# ps_adjustable_hv.net
KiCad netlist of a schematic drawn in EAGLE
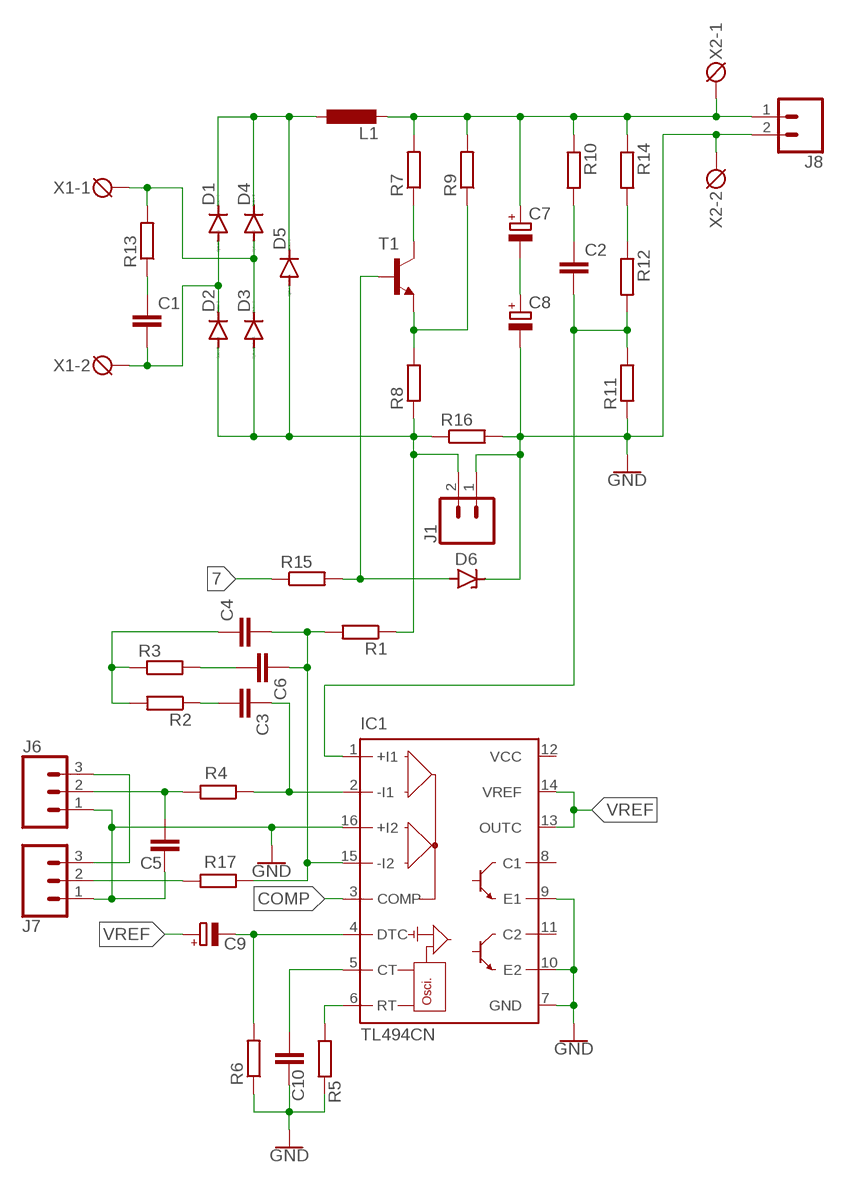
[diagram p0: schematic, sheet 1]

(export (version "E")
  (design (tool "Eeschema 10.0.6"))
  (components
    (comp (ref "C1")
      (value "C-EU050-045X075")
      (footprint "eagle-import:C050-045X075")
      (libsource (lib "eagle-import") (part "rcl_modify_C-EU050-045X075"))
    )
    (comp (ref "C2")
      (value "C-EU102-064X133")
      (footprint "eagle-import:C102-064X133")
      (libsource (lib "eagle-import") (part "rcl_modify_C-EU102-064X133"))
    )
    (comp (ref "C3")
      (value "C-EUC0805")
      (footprint "eagle-import:C0805")
      (libsource (lib "eagle-import") (part "C-EUC0805"))
    )
    (comp (ref "C4")
      (value "C-EUC0805")
      (footprint "eagle-import:C0805")
      (libsource (lib "eagle-import") (part "C-EUC0805"))
    )
    (comp (ref "C5")
      (value "C-EUC0805")
      (footprint "eagle-import:C0805")
      (libsource (lib "eagle-import") (part "C-EUC0805"))
    )
    (comp (ref "C6")
      (value "C-EUC0805")
      (footprint "eagle-import:C0805")
      (libsource (lib "eagle-import") (part "C-EUC0805"))
    )
    (comp (ref "C7")
      (value "CPOL-EUE10-20")
      (footprint "eagle-import:EB20D")
      (libsource (lib "eagle-import") (part "CPOL-EUE10-20"))
    )
    (comp (ref "C8")
      (value "CPOL-EUE10-20")
      (footprint "eagle-import:EB20D")
      (libsource (lib "eagle-import") (part "CPOL-EUE10-20"))
    )
    (comp (ref "C9")
      (value "CPOL-EUE2.5-6")
      (footprint "eagle-import:E2,5-6")
      (libsource (lib "eagle-import") (part "CPOL-EUE2.5-6"))
    )
    (comp (ref "C10")
      (value "C-EUC0805")
      (footprint "eagle-import:C0805")
      (libsource (lib "eagle-import") (part "C-EUC0805"))
    )
    (comp (ref "D1")
      (value "UF4003")
      (footprint "eagle-import:DO41-10")
      (libsource (lib "eagle-import") (part "UF4003"))
    )
    (comp (ref "D2")
      (value "UF4003")
      (footprint "eagle-import:DO41-10")
      (libsource (lib "eagle-import") (part "UF4003"))
    )
    (comp (ref "D3")
      (value "UF4003")
      (footprint "eagle-import:DO41-10")
      (libsource (lib "eagle-import") (part "UF4003"))
    )
    (comp (ref "D4")
      (value "UF4003")
      (footprint "eagle-import:DO41-10")
      (libsource (lib "eagle-import") (part "UF4003"))
    )
    (comp (ref "D5")
      (value "UF4003")
      (footprint "eagle-import:DO41-10")
      (libsource (lib "eagle-import") (part "UF4003"))
    )
    (comp (ref "D6")
      (value "ZENER-DIODEP1-Z12")
      (footprint "eagle-import:P1Z12")
      (libsource (lib "eagle-import") (part "ZENER-DIODEP1-Z12"))
    )
    (comp (ref "IC1")
      (value "TL494CN")
      (footprint "eagle-import:DIL16")
      (libsource (lib "eagle-import") (part "TL494NC"))
    )
    (comp (ref "J1")
      (value "CONN_02")
      (footprint "eagle-import:1X02")
      (libsource (lib "eagle-import") (part "CONN_02"))
    )
    (comp (ref "J6")
      (value "455-1750-1-ND")
      (footprint "eagle-import:1X03")
      (libsource (lib "eagle-import") (part "CONN_03"))
    )
    (comp (ref "J7")
      (value "455-1750-1-ND")
      (footprint "eagle-import:1X03")
      (libsource (lib "eagle-import") (part "CONN_03"))
    )
    (comp (ref "J8")
      (value "CONN_02")
      (footprint "eagle-import:1X02")
      (libsource (lib "eagle-import") (part "CONN_02"))
    )
    (comp (ref "L1")
      (value "L-EUTJ5-U1")
      (footprint "eagle-import:TJ5-U1")
      (libsource (lib "eagle-import") (part "L-EUTJ5-U1"))
    )
    (comp (ref "R1")
      (value "R-EU_R0805")
      (footprint "eagle-import:R0805")
      (libsource (lib "eagle-import") (part "R-EU_R0805"))
    )
    (comp (ref "R2")
      (value "R-EU_R0805")
      (footprint "eagle-import:R0805")
      (libsource (lib "eagle-import") (part "R-EU_R0805"))
    )
    (comp (ref "R3")
      (value "R-EU_VMTA55")
      (footprint "eagle-import:VMTA55")
      (libsource (lib "eagle-import") (part "rcl_modify_R-EU_VMTA55"))
    )
    (comp (ref "R4")
      (value "R-EU_VMTA55")
      (footprint "eagle-import:VMTA55")
      (libsource (lib "eagle-import") (part "rcl_modify_R-EU_VMTA55"))
    )
    (comp (ref "R5")
      (value "R-EU_R0805")
      (footprint "eagle-import:R0805")
      (libsource (lib "eagle-import") (part "R-EU_R0805"))
    )
    (comp (ref "R6")
      (value "R-EU_R0805")
      (footprint "eagle-import:R0805")
      (libsource (lib "eagle-import") (part "R-EU_R0805"))
    )
    (comp (ref "R7")
      (value "R-EU_VMTA55")
      (footprint "eagle-import:VMTA55")
      (libsource (lib "eagle-import") (part "rcl_modify_R-EU_VMTA55"))
    )
    (comp (ref "R8")
      (value "R-EU_VMTA55")
      (footprint "eagle-import:VMTA55")
      (libsource (lib "eagle-import") (part "rcl_modify_R-EU_VMTA55"))
    )
    (comp (ref "R9")
      (value "R-EU_VMTA55")
      (footprint "eagle-import:VMTA55")
      (libsource (lib "eagle-import") (part "rcl_modify_R-EU_VMTA55"))
    )
    (comp (ref "R10")
      (value "R-EU_VMTA55")
      (footprint "eagle-import:VMTA55")
      (libsource (lib "eagle-import") (part "rcl_modify_R-EU_VMTA55"))
    )
    (comp (ref "R11")
      (value "R-EU_VMTA55")
      (footprint "eagle-import:VMTA55")
      (libsource (lib "eagle-import") (part "rcl_modify_R-EU_VMTA55"))
    )
    (comp (ref "R12")
      (value "R-EU_VMTA55")
      (footprint "eagle-import:VMTA55")
      (libsource (lib "eagle-import") (part "rcl_modify_R-EU_VMTA55"))
    )
    (comp (ref "R13")
      (value "R-EU_VMTB60")
      (footprint "eagle-import:VMTB60")
      (libsource (lib "eagle-import") (part "rcl_modify_R-EU_VMTB60"))
    )
    (comp (ref "R14")
      (value "R-EU_VTA53")
      (footprint "eagle-import:VTA53")
      (libsource (lib "eagle-import") (part "rcl_modify_R-EU_VTA53"))
    )
    (comp (ref "R15")
      (value "R-EU_VMTA55")
      (footprint "eagle-import:VMTA55")
      (libsource (lib "eagle-import") (part "rcl_modify_R-EU_VMTA55"))
    )
    (comp (ref "R16")
      (value "R-EU_VTA53")
      (footprint "eagle-import:VTA53")
      (libsource (lib "eagle-import") (part "rcl_modify_R-EU_VTA53"))
    )
    (comp (ref "R17")
      (value "R-EU_VMTA55")
      (footprint "eagle-import:VMTA55")
      (libsource (lib "eagle-import") (part "rcl_modify_R-EU_VMTA55"))
    )
    (comp (ref "T1")
      (value "2N6517-NPN-TO92-CBE")
      (footprint "eagle-import:TO92-CBE")
      (libsource (lib "eagle-import") (part "-NPN-TO92-CBE2N6517"))
    )
    (comp (ref "X1")
      (value "DG3XX-02-5.0")
      (footprint "eagle-import:DG306-5.0-02P")
      (libsource (lib "eagle-import") (part "DG3XX-02-5.0"))
    )
    (comp (ref "X2")
      (value "DG3XX-02-5.0")
      (footprint "eagle-import:DG306-5.0-02P")
      (libsource (lib "eagle-import") (part "DG3XX-02-5.0"))
    )
  )
  (nets
    (net (code "1") (name "/VCC") (class "Default")
      (node (ref "IC1") (pin "12") (pinfunction "VCC_12") (pintype "power_in"))
    )
    (net (code "2") (name "7") (class "Default")
      (node (ref "R15") (pin "1") (pinfunction "1_1") (pintype "passive"))
    )
    (net (code "3") (name "COMP") (class "Default")
      (node (ref "IC1") (pin "3") (pinfunction "COMP_3") (pintype "passive"))
    )
    (net (code "4") (name "GND") (class "Default")
      (node (ref "C10") (pin "1") (pinfunction "1_1") (pintype "passive"))
      (node (ref "C5") (pin "2") (pinfunction "2_2") (pintype "passive"))
      (node (ref "C8") (pin "-") (pinfunction "-_-") (pintype "passive"))
      (node (ref "D6") (pin "C") (pinfunction "C_C") (pintype "passive"))
      (node (ref "IC1") (pin "10") (pinfunction "E2_10") (pintype "passive"))
      (node (ref "IC1") (pin "16") (pinfunction "+I2_16") (pintype "input"))
      (node (ref "IC1") (pin "7") (pinfunction "GND_7") (pintype "power_in"))
      (node (ref "IC1") (pin "9") (pinfunction "E1_9") (pintype "passive"))
      (node (ref "J1") (pin "1") (pinfunction "1_1") (pintype "passive"))
      (node (ref "J6") (pin "1") (pinfunction "1_1") (pintype "passive"))
      (node (ref "J7") (pin "1") (pinfunction "1_1") (pintype "passive"))
      (node (ref "J8") (pin "2") (pinfunction "2_2") (pintype "passive"))
      (node (ref "R11") (pin "1") (pinfunction "1_1") (pintype "passive"))
      (node (ref "R16") (pin "2") (pinfunction "2_2") (pintype "passive"))
      (node (ref "R5") (pin "2") (pinfunction "2_2") (pintype "passive"))
      (node (ref "R6") (pin "1") (pinfunction "1_1") (pintype "passive"))
      (node (ref "X2") (pin "2") (pinfunction "KL_2") (pintype "passive"))
    )
    (net (code "5") (name "Net-(C1-Pad1)") (class "Default")
      (node (ref "C1") (pin "1") (pinfunction "1_1") (pintype "passive"))
      (node (ref "R13") (pin "1") (pinfunction "1_1") (pintype "passive"))
    )
    (net (code "6") (name "Net-(C2-Pad1)") (class "Default")
      (node (ref "C2") (pin "1") (pinfunction "1_1") (pintype "passive"))
      (node (ref "R10") (pin "2") (pinfunction "2_2") (pintype "passive"))
    )
    (net (code "7") (name "Net-(C3-Pad2)") (class "Default")
      (node (ref "C3") (pin "2") (pinfunction "2_2") (pintype "passive"))
      (node (ref "R2") (pin "1") (pinfunction "1_1") (pintype "passive"))
    )
    (net (code "8") (name "Net-(C4-Pad1)") (class "Default")
      (node (ref "C4") (pin "1") (pinfunction "1_1") (pintype "passive"))
      (node (ref "R2") (pin "2") (pinfunction "2_2") (pintype "passive"))
      (node (ref "R3") (pin "1") (pinfunction "1_1") (pintype "passive"))
    )
    (net (code "9") (name "Net-(C5-Pad1)") (class "Default")
      (node (ref "C5") (pin "1") (pinfunction "1_1") (pintype "passive"))
      (node (ref "J6") (pin "2") (pinfunction "2_2") (pintype "passive"))
      (node (ref "R4") (pin "2") (pinfunction "2_2") (pintype "passive"))
    )
    (net (code "10") (name "Net-(C6-Pad2)") (class "Default")
      (node (ref "C6") (pin "2") (pinfunction "2_2") (pintype "passive"))
      (node (ref "R3") (pin "2") (pinfunction "2_2") (pintype "passive"))
    )
    (net (code "11") (name "Net-(C7-Pad-)") (class "Default")
      (node (ref "C7") (pin "-") (pinfunction "-_-") (pintype "passive"))
      (node (ref "C8") (pin "+") (pinfunction "+_+") (pintype "passive"))
    )
    (net (code "12") (name "Net-(D1-PadC)") (class "Default")
      (node (ref "D1") (pin "C") (pinfunction "C_C") (pintype "passive"))
      (node (ref "D4") (pin "C") (pinfunction "C_C") (pintype "passive"))
      (node (ref "D5") (pin "C") (pinfunction "C_C") (pintype "passive"))
      (node (ref "L1") (pin "1") (pinfunction "1_1") (pintype "passive"))
    )
    (net (code "13") (name "Net-(D2-PadA)") (class "Default")
      (node (ref "D2") (pin "A") (pinfunction "A_A") (pintype "passive"))
      (node (ref "D3") (pin "A") (pinfunction "A_A") (pintype "passive"))
      (node (ref "D5") (pin "A") (pinfunction "A_A") (pintype "passive"))
      (node (ref "J1") (pin "2") (pinfunction "2_2") (pintype "passive"))
      (node (ref "R1") (pin "1") (pinfunction "1_1") (pintype "passive"))
      (node (ref "R16") (pin "1") (pinfunction "1_1") (pintype "passive"))
      (node (ref "R8") (pin "1") (pinfunction "1_1") (pintype "passive"))
    )
    (net (code "14") (name "Net-(D6-PadA)") (class "Default")
      (node (ref "D6") (pin "A") (pinfunction "A_A") (pintype "passive"))
      (node (ref "R15") (pin "2") (pinfunction "2_2") (pintype "passive"))
      (node (ref "T1") (pin "B") (pinfunction "B_B") (pintype "passive"))
    )
    (net (code "15") (name "Net-(IC1-+I1)") (class "Default")
      (node (ref "C2") (pin "2") (pinfunction "2_2") (pintype "passive"))
      (node (ref "IC1") (pin "1") (pinfunction "+I1_1") (pintype "input"))
      (node (ref "R11") (pin "2") (pinfunction "2_2") (pintype "passive"))
      (node (ref "R12") (pin "2") (pinfunction "2_2") (pintype "passive"))
    )
    (net (code "16") (name "Net-(IC1--I1)") (class "Default")
      (node (ref "C3") (pin "1") (pinfunction "1_1") (pintype "passive"))
      (node (ref "IC1") (pin "2") (pinfunction "-I1_2") (pintype "input"))
      (node (ref "R4") (pin "1") (pinfunction "1_1") (pintype "passive"))
    )
    (net (code "17") (name "Net-(IC1--I2)") (class "Default")
      (node (ref "C4") (pin "2") (pinfunction "2_2") (pintype "passive"))
      (node (ref "C6") (pin "1") (pinfunction "1_1") (pintype "passive"))
      (node (ref "IC1") (pin "15") (pinfunction "-I2_15") (pintype "input"))
      (node (ref "R1") (pin "2") (pinfunction "2_2") (pintype "passive"))
      (node (ref "R17") (pin "1") (pinfunction "1_1") (pintype "passive"))
    )
    (net (code "18") (name "Net-(IC1-CT)") (class "Default")
      (node (ref "C10") (pin "2") (pinfunction "2_2") (pintype "passive"))
      (node (ref "IC1") (pin "5") (pinfunction "CT_5") (pintype "input"))
    )
    (net (code "19") (name "Net-(IC1-DTC)") (class "Default")
      (node (ref "C9") (pin "-") (pinfunction "-_-") (pintype "passive"))
      (node (ref "IC1") (pin "4") (pinfunction "DTC_4") (pintype "input"))
      (node (ref "R6") (pin "2") (pinfunction "2_2") (pintype "passive"))
    )
    (net (code "20") (name "Net-(IC1-RT)") (class "Default")
      (node (ref "IC1") (pin "6") (pinfunction "RT_6") (pintype "input"))
      (node (ref "R5") (pin "1") (pinfunction "1_1") (pintype "passive"))
    )
    (net (code "21") (name "Net-(J6-Pad3)") (class "Default")
      (node (ref "J6") (pin "3") (pinfunction "3_3") (pintype "passive"))
      (node (ref "J7") (pin "3") (pinfunction "3_3") (pintype "passive"))
    )
    (net (code "22") (name "Net-(J7-Pad2)") (class "Default")
      (node (ref "J7") (pin "2") (pinfunction "2_2") (pintype "passive"))
      (node (ref "R17") (pin "2") (pinfunction "2_2") (pintype "passive"))
    )
    (net (code "23") (name "Net-(R7-Pad1)") (class "Default")
      (node (ref "R7") (pin "1") (pinfunction "1_1") (pintype "passive"))
      (node (ref "T1") (pin "C") (pinfunction "C_C") (pintype "passive"))
    )
    (net (code "24") (name "Net-(R8-Pad2)") (class "Default")
      (node (ref "R8") (pin "2") (pinfunction "2_2") (pintype "passive"))
      (node (ref "R9") (pin "1") (pinfunction "1_1") (pintype "passive"))
      (node (ref "T1") (pin "E") (pinfunction "E_E") (pintype "passive"))
    )
    (net (code "25") (name "Net-(R12-Pad1)") (class "Default")
      (node (ref "R12") (pin "1") (pinfunction "1_1") (pintype "passive"))
      (node (ref "R14") (pin "2") (pinfunction "2_2") (pintype "passive"))
    )
    (net (code "26") (name "Net-(X1A-KL)") (class "Default")
      (node (ref "D3") (pin "C") (pinfunction "C_C") (pintype "passive"))
      (node (ref "D4") (pin "A") (pinfunction "A_A") (pintype "passive"))
      (node (ref "R13") (pin "2") (pinfunction "2_2") (pintype "passive"))
      (node (ref "X1") (pin "1") (pinfunction "KL_1") (pintype "passive"))
    )
    (net (code "27") (name "Net-(X1B-KL)") (class "Default")
      (node (ref "C1") (pin "2") (pinfunction "2_2") (pintype "passive"))
      (node (ref "D1") (pin "A") (pinfunction "A_A") (pintype "passive"))
      (node (ref "D2") (pin "C") (pinfunction "C_C") (pintype "passive"))
      (node (ref "X1") (pin "2") (pinfunction "KL_2") (pintype "passive"))
    )
    (net (code "28") (name "Net-(X2A-KL)") (class "Default")
      (node (ref "C7") (pin "+") (pinfunction "+_+") (pintype "passive"))
      (node (ref "J8") (pin "1") (pinfunction "1_1") (pintype "passive"))
      (node (ref "L1") (pin "2") (pinfunction "2_2") (pintype "passive"))
      (node (ref "R10") (pin "1") (pinfunction "1_1") (pintype "passive"))
      (node (ref "R14") (pin "1") (pinfunction "1_1") (pintype "passive"))
      (node (ref "R7") (pin "2") (pinfunction "2_2") (pintype "passive"))
      (node (ref "R9") (pin "2") (pinfunction "2_2") (pintype "passive"))
      (node (ref "X2") (pin "1") (pinfunction "KL_1") (pintype "passive"))
    )
    (net (code "29") (name "VREF") (class "Default")
      (node (ref "C9") (pin "+") (pinfunction "+_+") (pintype "passive"))
      (node (ref "IC1") (pin "13") (pinfunction "OUTC_13") (pintype "output"))
      (node (ref "IC1") (pin "14") (pinfunction "VREF_14") (pintype "input"))
    )
    (net (code "30") (name "unconnected-(IC1-C1-Pad8)") (class "Default")
      (node (ref "IC1") (pin "8") (pinfunction "C1_8") (pintype "passive"))
    )
    (net (code "31") (name "unconnected-(IC1-C2-Pad11)") (class "Default")
      (node (ref "IC1") (pin "11") (pinfunction "C2_11") (pintype "passive"))
    )
  )
)
